# pidshield-mk-1.net
KiCad netlist of a schematic drawn in EAGLE
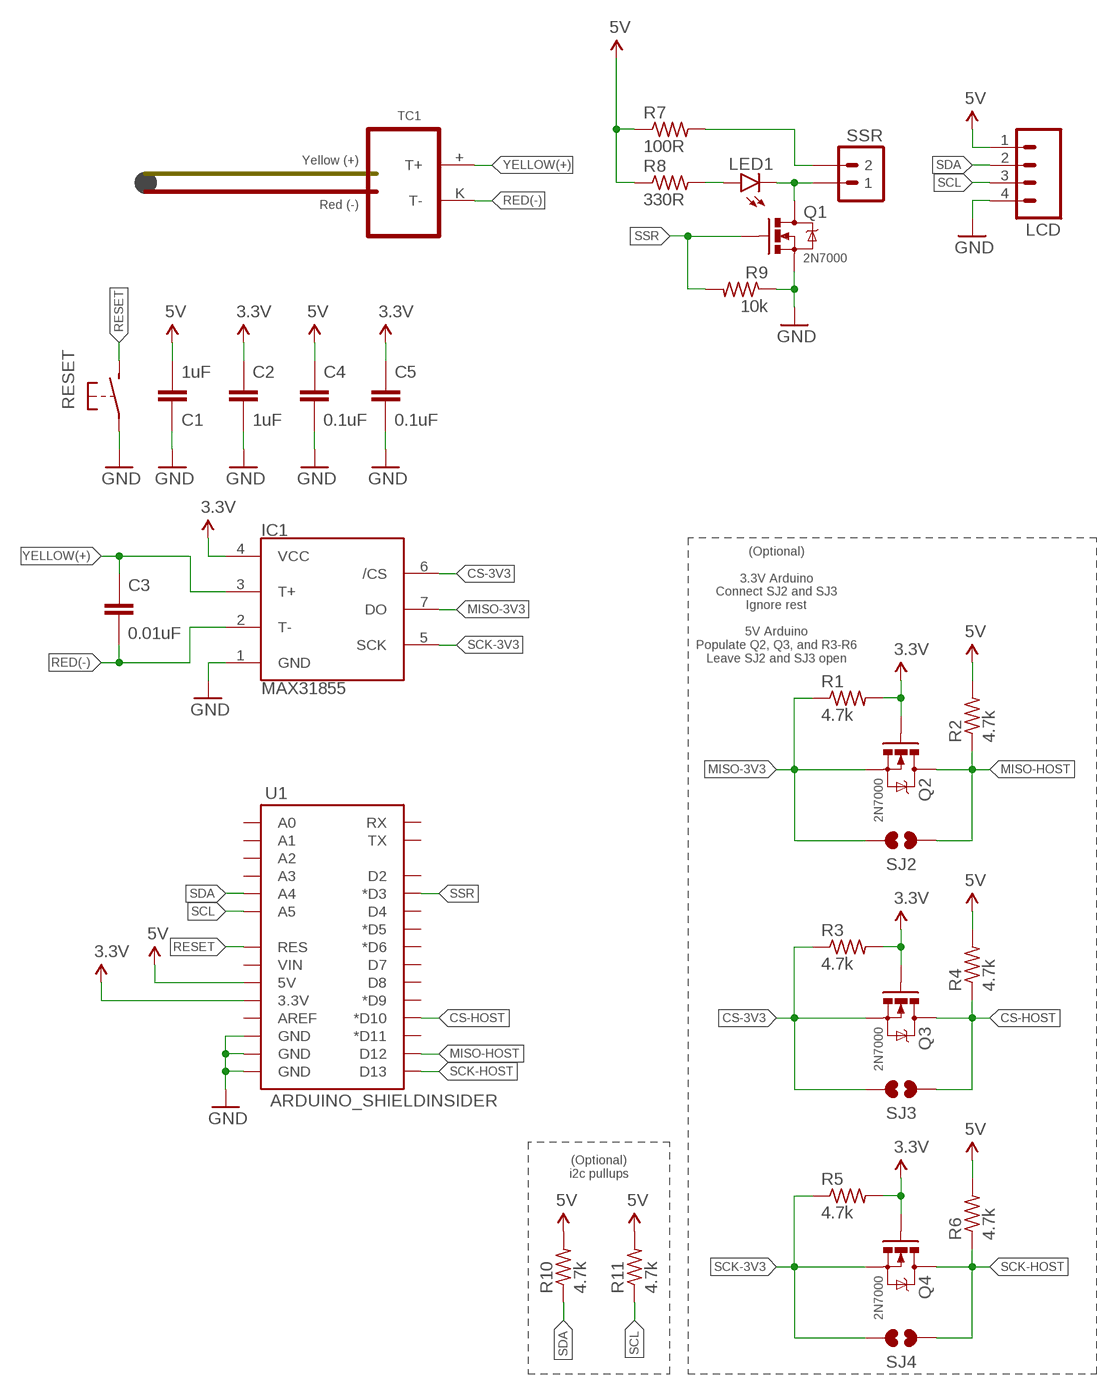
[diagram p0: schematic, sheet 1]

(export (version "E")
  (design (tool "Eeschema 10.0.6"))
  (components
    (comp (ref "C1")
      (value "1uF")
      (footprint "eagle-import:C025-024X044")
      (libsource (lib "eagle-import") (part "CAPACITOR-CERAMIC025-024X044"))
    )
    (comp (ref "C2")
      (value "1uF")
      (footprint "eagle-import:C025-024X044")
      (libsource (lib "eagle-import") (part "CAPACITOR-CERAMIC025-024X044"))
    )
    (comp (ref "C3")
      (value "0.01uF")
      (footprint "eagle-import:C025-024X044")
      (libsource (lib "eagle-import") (part "CAPACITOR-CERAMIC025-024X044"))
    )
    (comp (ref "C4")
      (value "0.1uF")
      (footprint "eagle-import:C025-024X044")
      (libsource (lib "eagle-import") (part "CAPACITOR-CERAMIC025-024X044"))
    )
    (comp (ref "C5")
      (value "0.1uF")
      (footprint "eagle-import:C025-024X044")
      (libsource (lib "eagle-import") (part "CAPACITOR-CERAMIC025-024X044"))
    )
    (comp (ref "IC1")
      (value "MAX31855")
      (footprint "eagle-import:SOIC127P600X175-8N")
      (libsource (lib "eagle-import") (part "MAX31855SOIC"))
    )
    (comp (ref "LCD")
      (value "M04JST_XH_RA")
      (footprint "eagle-import:JST-4-XH-RA-PTH")
      (libsource (lib "eagle-import") (part "M04JST_XH_RA"))
    )
    (comp (ref "LED1")
      (value "LED3MM")
      (footprint "eagle-import:LED3MM")
      (libsource (lib "eagle-import") (part "LED3MM"))
    )
    (comp (ref "Q1")
      (value "2N7000")
      (footprint "eagle-import:TO-92-AMMO")
      (libsource (lib "eagle-import") (part "MOSFET-NCHANNEL2N7000-AMMO"))
    )
    (comp (ref "Q2")
      (value "2N7000")
      (footprint "eagle-import:TO-92-AMMO")
      (libsource (lib "eagle-import") (part "MOSFET-NCHANNEL2N7000-AMMO"))
    )
    (comp (ref "Q3")
      (value "2N7000")
      (footprint "eagle-import:TO-92-AMMO")
      (libsource (lib "eagle-import") (part "MOSFET-NCHANNEL2N7000-AMMO"))
    )
    (comp (ref "Q4")
      (value "2N7000")
      (footprint "eagle-import:TO-92-AMMO")
      (libsource (lib "eagle-import") (part "MOSFET-NCHANNEL2N7000-AMMO"))
    )
    (comp (ref "R1")
      (value "4.7k")
      (footprint "eagle-import:RESISTOR-AXIAL-PTH-6.35MM")
      (libsource (lib "eagle-import") (part "RESISTORPTH-AXIAL-6.35MM"))
    )
    (comp (ref "R2")
      (value "4.7k")
      (footprint "eagle-import:RESISTOR-AXIAL-PTH-6.35MM")
      (libsource (lib "eagle-import") (part "RESISTORPTH-AXIAL-6.35MM"))
    )
    (comp (ref "R3")
      (value "4.7k")
      (footprint "eagle-import:RESISTOR-AXIAL-PTH-6.35MM")
      (libsource (lib "eagle-import") (part "RESISTORPTH-AXIAL-6.35MM"))
    )
    (comp (ref "R4")
      (value "4.7k")
      (footprint "eagle-import:RESISTOR-AXIAL-PTH-6.35MM")
      (libsource (lib "eagle-import") (part "RESISTORPTH-AXIAL-6.35MM"))
    )
    (comp (ref "R5")
      (value "4.7k")
      (footprint "eagle-import:RESISTOR-AXIAL-PTH-6.35MM")
      (libsource (lib "eagle-import") (part "RESISTORPTH-AXIAL-6.35MM"))
    )
    (comp (ref "R6")
      (value "4.7k")
      (footprint "eagle-import:RESISTOR-AXIAL-PTH-6.35MM")
      (libsource (lib "eagle-import") (part "RESISTORPTH-AXIAL-6.35MM"))
    )
    (comp (ref "R7")
      (value "100R")
      (footprint "eagle-import:RESISTOR-AXIAL-PTH-6.35MM")
      (libsource (lib "eagle-import") (part "RESISTORPTH-AXIAL-6.35MM"))
    )
    (comp (ref "R8")
      (value "330R")
      (footprint "eagle-import:RESISTOR-AXIAL-PTH-6.35MM")
      (libsource (lib "eagle-import") (part "RESISTORPTH-AXIAL-6.35MM"))
    )
    (comp (ref "R9")
      (value "10k")
      (footprint "eagle-import:RESISTOR-AXIAL-PTH-6.35MM")
      (libsource (lib "eagle-import") (part "RESISTORPTH-AXIAL-6.35MM"))
    )
    (comp (ref "R10")
      (value "4.7k")
      (footprint "eagle-import:RESISTOR-AXIAL-PTH-6.35MM")
      (libsource (lib "eagle-import") (part "RESISTORPTH-AXIAL-6.35MM"))
    )
    (comp (ref "R11")
      (value "4.7k")
      (footprint "eagle-import:RESISTOR-AXIAL-PTH-6.35MM")
      (libsource (lib "eagle-import") (part "RESISTORPTH-AXIAL-6.35MM"))
    )
    (comp (ref "RESET")
      (value "SPST-NO-TACT3MM-RA")
      (footprint "eagle-import:TACTILE-PTH-SIDE")
      (libsource (lib "eagle-import") (part "SPST-NO-TACT3MM-RA"))
    )
    (comp (ref "SJ2")
      (value "JUMPER-PAD-2-NOYES_SILK")
      (footprint "eagle-import:PAD-JUMPER-2-NO_YES_SILK")
      (libsource (lib "eagle-import") (part "JUMPER-PAD-2-NOYES_SILK"))
    )
    (comp (ref "SJ3")
      (value "JUMPER-PAD-2-NOYES_SILK")
      (footprint "eagle-import:PAD-JUMPER-2-NO_YES_SILK")
      (libsource (lib "eagle-import") (part "JUMPER-PAD-2-NOYES_SILK"))
    )
    (comp (ref "SJ4")
      (value "JUMPER-PAD-2-NOYES_SILK")
      (footprint "eagle-import:PAD-JUMPER-2-NO_YES_SILK")
      (libsource (lib "eagle-import") (part "JUMPER-PAD-2-NOYES_SILK"))
    )
    (comp (ref "SSR")
      (value "M02JST-PTH-RA-SMALLPADS")
      (footprint "eagle-import:JST-2-PH-RA-PTH-SMALLPADS")
      (libsource (lib "eagle-import") (part "M02JST-PTH-RA-SMALLPADS"))
    )
    (comp (ref "TC1")
      (value "PCC-SMP-K")
      (footprint "eagle-import:PCC-SMP")
      (libsource (lib "eagle-import") (part "THERMOCOUPLE-CONNECTORMINI-PCB"))
    )
    (comp (ref "U1")
      (value "ARDUINO_SHIELDINSIDER")
      (footprint "eagle-import:ARDUINO_SHIELD_NOOUTLINE_INSIDE")
      (libsource (lib "eagle-import") (part "ARDUINO_SHIELDINSIDER"))
    )
  )
  (nets
    (net (code "1") (name "3.3V") (class "Default")
      (node (ref "C2") (pin "1") (pinfunction "1_1") (pintype "passive"))
      (node (ref "C5") (pin "1") (pinfunction "1_1") (pintype "passive"))
      (node (ref "IC1") (pin "4") (pinfunction "VCC_4") (pintype "power_in"))
      (node (ref "Q2") (pin "2") (pinfunction "G_2") (pintype "passive"))
      (node (ref "Q3") (pin "2") (pinfunction "G_2") (pintype "passive"))
      (node (ref "Q4") (pin "2") (pinfunction "G_2") (pintype "passive"))
      (node (ref "R1") (pin "P$2") (pinfunction "2_P$2") (pintype "passive"))
      (node (ref "R3") (pin "P$2") (pinfunction "2_P$2") (pintype "passive"))
      (node (ref "R5") (pin "P$2") (pinfunction "2_P$2") (pintype "passive"))
      (node (ref "U1") (pin "3.3V") (pinfunction "3.3V_3.3V") (pintype "bidirectional"))
    )
    (net (code "2") (name "5V") (class "Default")
      (node (ref "C1") (pin "2") (pinfunction "2_2") (pintype "passive"))
      (node (ref "C4") (pin "1") (pinfunction "1_1") (pintype "passive"))
      (node (ref "LCD") (pin "1") (pinfunction "1_1") (pintype "passive"))
      (node (ref "R10") (pin "P$2") (pinfunction "2_P$2") (pintype "passive"))
      (node (ref "R11") (pin "P$2") (pinfunction "2_P$2") (pintype "passive"))
      (node (ref "R2") (pin "P$2") (pinfunction "2_P$2") (pintype "passive"))
      (node (ref "R4") (pin "P$2") (pinfunction "2_P$2") (pintype "passive"))
      (node (ref "R6") (pin "P$2") (pinfunction "2_P$2") (pintype "passive"))
      (node (ref "R7") (pin "P$1") (pinfunction "1_P$1") (pintype "passive"))
      (node (ref "R8") (pin "P$1") (pinfunction "1_P$1") (pintype "passive"))
      (node (ref "U1") (pin "5V") (pinfunction "5V_5V") (pintype "bidirectional"))
    )
    (net (code "3") (name "CS-3V3") (class "Default")
      (node (ref "IC1") (pin "6") (pinfunction "/CS_6") (pintype "input"))
      (node (ref "Q3") (pin "1") (pinfunction "S_1") (pintype "passive"))
      (node (ref "R3") (pin "P$1") (pinfunction "1_P$1") (pintype "passive"))
      (node (ref "SJ3") (pin "2") (pinfunction "2_2") (pintype "passive"))
    )
    (net (code "4") (name "CS-HOST") (class "Default")
      (node (ref "Q3") (pin "3") (pinfunction "D_3") (pintype "passive"))
      (node (ref "R4") (pin "P$1") (pinfunction "1_P$1") (pintype "passive"))
      (node (ref "SJ3") (pin "1") (pinfunction "1_1") (pintype "passive"))
      (node (ref "U1") (pin "D10") (pinfunction "*D10_D10") (pintype "bidirectional"))
    )
    (net (code "5") (name "GND") (class "Default")
      (node (ref "C1") (pin "1") (pinfunction "1_1") (pintype "passive"))
      (node (ref "C2") (pin "2") (pinfunction "2_2") (pintype "passive"))
      (node (ref "C4") (pin "2") (pinfunction "2_2") (pintype "passive"))
      (node (ref "C5") (pin "2") (pinfunction "2_2") (pintype "passive"))
      (node (ref "IC1") (pin "1") (pinfunction "GND_1") (pintype "power_in"))
      (node (ref "LCD") (pin "4") (pinfunction "4_4") (pintype "passive"))
      (node (ref "Q1") (pin "1") (pinfunction "S_1") (pintype "passive"))
      (node (ref "R9") (pin "P$1") (pinfunction "1_P$1") (pintype "passive"))
      (node (ref "RESET") (pin "1") (pinfunction "1_1") (pintype "passive"))
      (node (ref "U1") (pin "GND@0") (pinfunction "GND_GND@0") (pintype "bidirectional"))
      (node (ref "U1") (pin "GND@1") (pinfunction "GND_GND@1") (pintype "bidirectional"))
      (node (ref "U1") (pin "GND@2") (pinfunction "GND_GND@2") (pintype "bidirectional"))
    )
    (net (code "6") (name "MISO-3V3") (class "Default")
      (node (ref "IC1") (pin "7") (pinfunction "DO_7") (pintype "output"))
      (node (ref "Q2") (pin "1") (pinfunction "S_1") (pintype "passive"))
      (node (ref "R1") (pin "P$1") (pinfunction "1_P$1") (pintype "passive"))
      (node (ref "SJ2") (pin "2") (pinfunction "2_2") (pintype "passive"))
    )
    (net (code "7") (name "MISO-HOST") (class "Default")
      (node (ref "Q2") (pin "3") (pinfunction "D_3") (pintype "passive"))
      (node (ref "R2") (pin "P$1") (pinfunction "1_P$1") (pintype "passive"))
      (node (ref "SJ2") (pin "1") (pinfunction "1_1") (pintype "passive"))
      (node (ref "U1") (pin "D12") (pinfunction "D12_D12") (pintype "bidirectional"))
    )
    (net (code "8") (name "Net-(LED1-C)") (class "Default")
      (node (ref "LED1") (pin "K") (pinfunction "C_K") (pintype "passive"))
      (node (ref "Q1") (pin "3") (pinfunction "D_3") (pintype "passive"))
      (node (ref "SSR") (pin "1") (pinfunction "1_1") (pintype "passive"))
    )
    (net (code "9") (name "Net-(R7-2)") (class "Default")
      (node (ref "R7") (pin "P$2") (pinfunction "2_P$2") (pintype "passive"))
      (node (ref "SSR") (pin "2") (pinfunction "2_2") (pintype "passive"))
    )
    (net (code "10") (name "Net-(R8-2)") (class "Default")
      (node (ref "LED1") (pin "A") (pinfunction "A_A") (pintype "passive"))
      (node (ref "R8") (pin "P$2") (pinfunction "2_P$2") (pintype "passive"))
    )
    (net (code "11") (name "RED(-)") (class "Default")
      (node (ref "C3") (pin "2") (pinfunction "2_2") (pintype "passive"))
      (node (ref "IC1") (pin "2") (pinfunction "T-_2") (pintype "input"))
      (node (ref "TC1") (pin "K") (pinfunction "T-_K") (pintype "bidirectional"))
    )
    (net (code "12") (name "RESET") (class "Default")
      (node (ref "RESET") (pin "2") (pinfunction "2_2") (pintype "passive"))
      (node (ref "U1") (pin "RES") (pinfunction "RES_RES") (pintype "bidirectional"))
    )
    (net (code "13") (name "SCK-3V3") (class "Default")
      (node (ref "IC1") (pin "5") (pinfunction "SCK_5") (pintype "input"))
      (node (ref "Q4") (pin "1") (pinfunction "S_1") (pintype "passive"))
      (node (ref "R5") (pin "P$1") (pinfunction "1_P$1") (pintype "passive"))
      (node (ref "SJ4") (pin "2") (pinfunction "2_2") (pintype "passive"))
    )
    (net (code "14") (name "SCK-HOST") (class "Default")
      (node (ref "Q4") (pin "3") (pinfunction "D_3") (pintype "passive"))
      (node (ref "R6") (pin "P$1") (pinfunction "1_P$1") (pintype "passive"))
      (node (ref "SJ4") (pin "1") (pinfunction "1_1") (pintype "passive"))
      (node (ref "U1") (pin "D13") (pinfunction "D13_D13") (pintype "bidirectional"))
    )
    (net (code "15") (name "SCL") (class "Default")
      (node (ref "LCD") (pin "3") (pinfunction "3_3") (pintype "passive"))
      (node (ref "R11") (pin "P$1") (pinfunction "1_P$1") (pintype "passive"))
      (node (ref "U1") (pin "A5") (pinfunction "A5_A5") (pintype "bidirectional"))
    )
    (net (code "16") (name "SDA") (class "Default")
      (node (ref "LCD") (pin "2") (pinfunction "2_2") (pintype "passive"))
      (node (ref "R10") (pin "P$1") (pinfunction "1_P$1") (pintype "passive"))
      (node (ref "U1") (pin "A4") (pinfunction "A4_A4") (pintype "bidirectional"))
    )
    (net (code "17") (name "SSR") (class "Default")
      (node (ref "Q1") (pin "2") (pinfunction "G_2") (pintype "passive"))
      (node (ref "R9") (pin "P$2") (pinfunction "2_P$2") (pintype "passive"))
      (node (ref "U1") (pin "D3") (pinfunction "*D3_D3") (pintype "bidirectional"))
    )
    (net (code "18") (name "YELLOW(+)") (class "Default")
      (node (ref "C3") (pin "1") (pinfunction "1_1") (pintype "passive"))
      (node (ref "IC1") (pin "3") (pinfunction "T+_3") (pintype "input"))
      (node (ref "TC1") (pin "+") (pinfunction "T+_+") (pintype "bidirectional"))
    )
    (net (code "19") (name "unconnected-(U1-*D5-PadD5)") (class "Default")
      (node (ref "U1") (pin "D5") (pinfunction "*D5_D5") (pintype "bidirectional"))
    )
    (net (code "20") (name "unconnected-(U1-*D6-PadD6)") (class "Default")
      (node (ref "U1") (pin "D6") (pinfunction "*D6_D6") (pintype "bidirectional"))
    )
    (net (code "21") (name "unconnected-(U1-*D9-PadD9)") (class "Default")
      (node (ref "U1") (pin "D9") (pinfunction "*D9_D9") (pintype "bidirectional"))
    )
    (net (code "22") (name "unconnected-(U1-*D11-PadD11)") (class "Default")
      (node (ref "U1") (pin "D11") (pinfunction "*D11_D11") (pintype "bidirectional"))
    )
    (net (code "23") (name "unconnected-(U1-PadA0)") (class "Default")
      (node (ref "U1") (pin "A0") (pinfunction "A0_A0") (pintype "bidirectional"))
    )
    (net (code "24") (name "unconnected-(U1-PadA1)") (class "Default")
      (node (ref "U1") (pin "A1") (pinfunction "A1_A1") (pintype "bidirectional"))
    )
    (net (code "25") (name "unconnected-(U1-PadA2)") (class "Default")
      (node (ref "U1") (pin "A2") (pinfunction "A2_A2") (pintype "bidirectional"))
    )
    (net (code "26") (name "unconnected-(U1-PadA3)") (class "Default")
      (node (ref "U1") (pin "A3") (pinfunction "A3_A3") (pintype "bidirectional"))
    )
    (net (code "27") (name "unconnected-(U1-PadAREF)") (class "Default")
      (node (ref "U1") (pin "AREF") (pinfunction "AREF_AREF") (pintype "bidirectional"))
    )
    (net (code "28") (name "unconnected-(U1-PadD2)") (class "Default")
      (node (ref "U1") (pin "D2") (pinfunction "D2_D2") (pintype "bidirectional"))
    )
    (net (code "29") (name "unconnected-(U1-PadD4)") (class "Default")
      (node (ref "U1") (pin "D4") (pinfunction "D4_D4") (pintype "bidirectional"))
    )
    (net (code "30") (name "unconnected-(U1-PadD7)") (class "Default")
      (node (ref "U1") (pin "D7") (pinfunction "D7_D7") (pintype "bidirectional"))
    )
    (net (code "31") (name "unconnected-(U1-PadD8)") (class "Default")
      (node (ref "U1") (pin "D8") (pinfunction "D8_D8") (pintype "bidirectional"))
    )
    (net (code "32") (name "unconnected-(U1-PadRX)") (class "Default")
      (node (ref "U1") (pin "RX") (pinfunction "RX_RX") (pintype "bidirectional"))
    )
    (net (code "33") (name "unconnected-(U1-PadTX)") (class "Default")
      (node (ref "U1") (pin "TX") (pinfunction "TX_TX") (pintype "bidirectional"))
    )
    (net (code "34") (name "unconnected-(U1-PadVIN)") (class "Default")
      (node (ref "U1") (pin "VIN") (pinfunction "VIN_VIN") (pintype "bidirectional"))
    )
  )
)
